# l-drv_h1.net
KiCad netlist of a schematic drawn in EAGLE
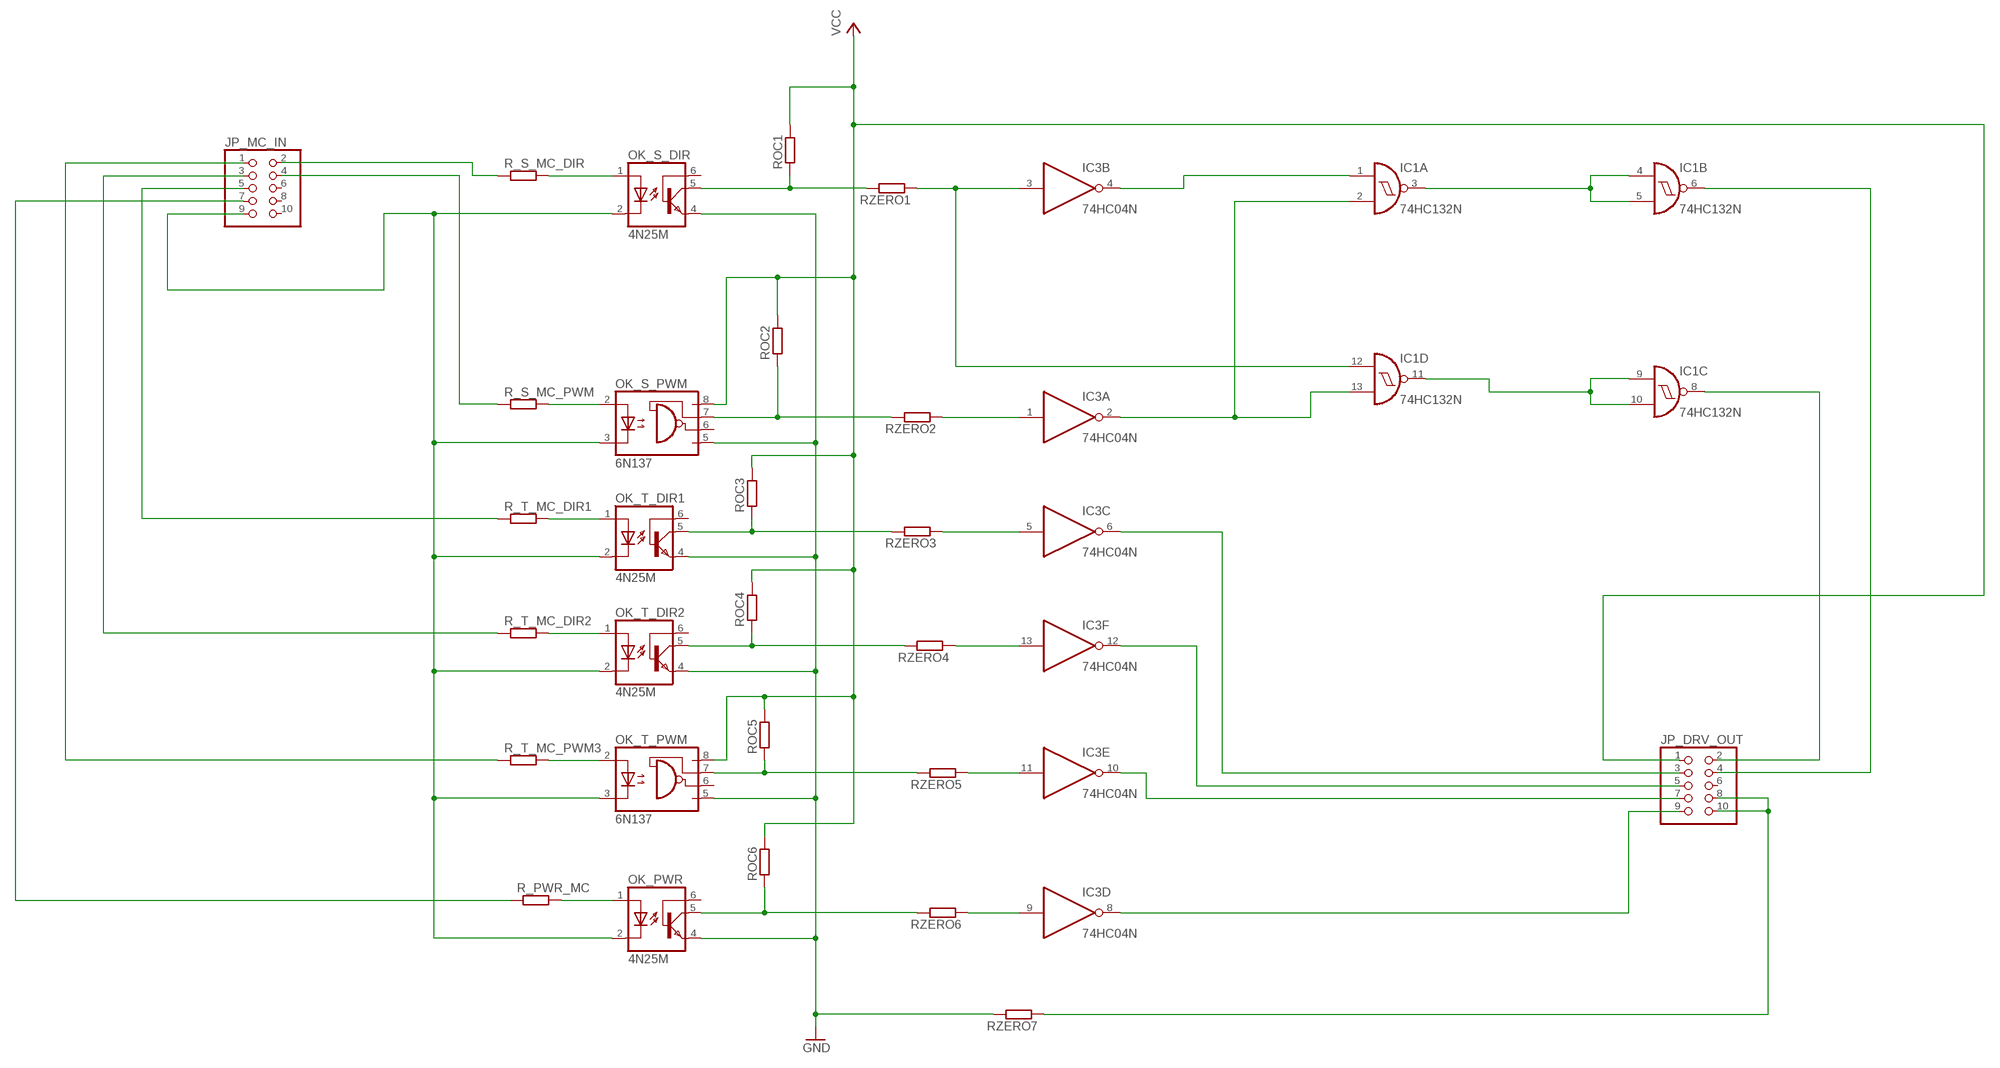
[diagram p0: schematic, sheet 1]

(export (version "E")
  (design (tool "Eeschema 10.0.6"))
  (components
    (comp (ref "IC1")
      (value "74HC132N")
      (footprint "eagle-import:DIL14")
      (libsource (lib "eagle-import") (part "74132NHC"))
    )
    (comp (ref "IC3")
      (value "74HC04N")
      (footprint "eagle-import:DIL14")
      (libsource (lib "eagle-import") (part "7404NHC"))
    )
    (comp (ref "JP_DRV_OUT")
      (value "PINHD-2X5/90")
      (footprint "eagle-import:2X05_90")
      (libsource (lib "eagle-import") (part "PINHD-2X5/90"))
    )
    (comp (ref "JP_MC_IN")
      (value "PINHD-2X5")
      (footprint "eagle-import:2X05")
      (libsource (lib "eagle-import") (part "PINHD-2X5"))
    )
    (comp (ref "OK_PWR")
      (value "4N25M")
      (footprint "eagle-import:DIL06")
      (fields (field (name "MPN") "4N25-M"))
      (libsource (lib "eagle-import") (part "4N?M25"))
    )
    (comp (ref "OK_S_DIR")
      (value "4N25M")
      (footprint "eagle-import:DIL06")
      (fields (field (name "MPN") "4N25-M"))
      (libsource (lib "eagle-import") (part "4N?M25"))
    )
    (comp (ref "OK_S_PWM")
      (value "6N137")
      (footprint "eagle-import:DIL08")
      (libsource (lib "eagle-import") (part "6N137"))
    )
    (comp (ref "OK_T_DIR1")
      (value "4N25M")
      (footprint "eagle-import:DIL06")
      (fields (field (name "MPN") "4N25-M"))
      (libsource (lib "eagle-import") (part "4N?M25"))
    )
    (comp (ref "OK_T_DIR2")
      (value "4N25M")
      (footprint "eagle-import:DIL06")
      (fields (field (name "MPN") "4N25-M"))
      (libsource (lib "eagle-import") (part "4N?M25"))
    )
    (comp (ref "OK_T_PWM")
      (value "6N137")
      (footprint "eagle-import:DIL08")
      (libsource (lib "eagle-import") (part "6N137"))
    )
    (comp (ref "ROC1")
      (value "R-EU_0204/5")
      (footprint "eagle-import:0204_5")
      (libsource (lib "eagle-import") (part "R-EU_0204/5"))
    )
    (comp (ref "ROC2")
      (value "R-EU_0204/5")
      (footprint "eagle-import:0204_5")
      (libsource (lib "eagle-import") (part "R-EU_0204/5"))
    )
    (comp (ref "ROC3")
      (value "R-EU_0204/5")
      (footprint "eagle-import:0204_5")
      (libsource (lib "eagle-import") (part "R-EU_0204/5"))
    )
    (comp (ref "ROC4")
      (value "R-EU_0204/5")
      (footprint "eagle-import:0204_5")
      (libsource (lib "eagle-import") (part "R-EU_0204/5"))
    )
    (comp (ref "ROC5")
      (value "R-EU_0204/5")
      (footprint "eagle-import:0204_5")
      (libsource (lib "eagle-import") (part "R-EU_0204/5"))
    )
    (comp (ref "ROC6")
      (value "R-EU_0204/5")
      (footprint "eagle-import:0204_5")
      (libsource (lib "eagle-import") (part "R-EU_0204/5"))
    )
    (comp (ref "RZERO1")
      (value "R-EU_0204/5")
      (footprint "eagle-import:0204_5")
      (libsource (lib "eagle-import") (part "R-EU_0204/5"))
    )
    (comp (ref "RZERO2")
      (value "R-EU_0204/5")
      (footprint "eagle-import:0204_5")
      (libsource (lib "eagle-import") (part "R-EU_0204/5"))
    )
    (comp (ref "RZERO3")
      (value "R-EU_0204/5")
      (footprint "eagle-import:0204_5")
      (libsource (lib "eagle-import") (part "R-EU_0204/5"))
    )
    (comp (ref "RZERO4")
      (value "R-EU_0204/5")
      (footprint "eagle-import:0204_5")
      (libsource (lib "eagle-import") (part "R-EU_0204/5"))
    )
    (comp (ref "RZERO5")
      (value "R-EU_0204/5")
      (footprint "eagle-import:0204_5")
      (libsource (lib "eagle-import") (part "R-EU_0204/5"))
    )
    (comp (ref "RZERO6")
      (value "R-EU_0204/5")
      (footprint "eagle-import:0204_5")
      (libsource (lib "eagle-import") (part "R-EU_0204/5"))
    )
    (comp (ref "RZERO7")
      (value "R-EU_0204/5")
      (footprint "eagle-import:0204_5")
      (libsource (lib "eagle-import") (part "R-EU_0204/5"))
    )
    (comp (ref "R_PWR_MC")
      (value "R-EU_0204/5")
      (footprint "eagle-import:0204_5")
      (libsource (lib "eagle-import") (part "R-EU_0204/5"))
    )
    (comp (ref "R_S_MC_DIR")
      (value "R-EU_0204/5")
      (footprint "eagle-import:0204_5")
      (libsource (lib "eagle-import") (part "R-EU_0204/5"))
    )
    (comp (ref "R_S_MC_PWM")
      (value "R-EU_0204/5")
      (footprint "eagle-import:0204_5")
      (libsource (lib "eagle-import") (part "R-EU_0204/5"))
    )
    (comp (ref "R_T_MC_DIR1")
      (value "R-EU_0204/5")
      (footprint "eagle-import:0204_5")
      (libsource (lib "eagle-import") (part "R-EU_0204/5"))
    )
    (comp (ref "R_T_MC_DIR2")
      (value "R-EU_0204/5")
      (footprint "eagle-import:0204_5")
      (libsource (lib "eagle-import") (part "R-EU_0204/5"))
    )
    (comp (ref "R_T_MC_PWM3")
      (value "R-EU_0204/5")
      (footprint "eagle-import:0204_5")
      (libsource (lib "eagle-import") (part "R-EU_0204/5"))
    )
  )
  (nets
    (net (code "1") (name "GND") (class "Default")
      (node (ref "OK_PWR") (pin "4") (pinfunction "EMI_4") (pintype "passive"))
      (node (ref "OK_S_DIR") (pin "4") (pinfunction "EMI_4") (pintype "passive"))
      (node (ref "OK_S_PWM") (pin "5") (pinfunction "GND_5") (pintype "passive"))
      (node (ref "OK_T_DIR1") (pin "4") (pinfunction "EMI_4") (pintype "passive"))
      (node (ref "OK_T_DIR2") (pin "4") (pinfunction "EMI_4") (pintype "passive"))
      (node (ref "OK_T_PWM") (pin "5") (pinfunction "GND_5") (pintype "passive"))
      (node (ref "RZERO7") (pin "2") (pinfunction "2_2") (pintype "passive"))
    )
    (net (code "2") (name "Net-(IC1A-I0)") (class "Default")
      (node (ref "IC1") (pin "1") (pinfunction "I0_1") (pintype "input"))
      (node (ref "IC3") (pin "4") (pinfunction "O_4") (pintype "output"))
    )
    (net (code "3") (name "Net-(IC1A-I1)") (class "Default")
      (node (ref "IC1") (pin "13") (pinfunction "I1_13") (pintype "input"))
      (node (ref "IC1") (pin "2") (pinfunction "I1_2") (pintype "input"))
      (node (ref "IC3") (pin "2") (pinfunction "O_2") (pintype "output"))
    )
    (net (code "4") (name "Net-(IC1A-O)") (class "Default")
      (node (ref "IC1") (pin "3") (pinfunction "O_3") (pintype "output"))
      (node (ref "IC1") (pin "4") (pinfunction "I0_4") (pintype "input"))
      (node (ref "IC1") (pin "5") (pinfunction "I1_5") (pintype "input"))
    )
    (net (code "5") (name "Net-(IC1B-O)") (class "Default")
      (node (ref "IC1") (pin "6") (pinfunction "O_6") (pintype "output"))
      (node (ref "JP_DRV_OUT") (pin "4") (pinfunction "4_4") (pintype "passive"))
    )
    (net (code "6") (name "Net-(IC1C-I0)") (class "Default")
      (node (ref "IC1") (pin "10") (pinfunction "I1_10") (pintype "input"))
      (node (ref "IC1") (pin "11") (pinfunction "O_11") (pintype "output"))
      (node (ref "IC1") (pin "9") (pinfunction "I0_9") (pintype "input"))
    )
    (net (code "7") (name "Net-(IC1C-O)") (class "Default")
      (node (ref "IC1") (pin "8") (pinfunction "O_8") (pintype "output"))
      (node (ref "JP_DRV_OUT") (pin "2") (pinfunction "2_2") (pintype "passive"))
    )
    (net (code "8") (name "Net-(IC1D-I0)") (class "Default")
      (node (ref "IC1") (pin "12") (pinfunction "I0_12") (pintype "input"))
      (node (ref "IC3") (pin "3") (pinfunction "I_3") (pintype "input"))
      (node (ref "RZERO1") (pin "1") (pinfunction "1_1") (pintype "passive"))
    )
    (net (code "9") (name "Net-(IC3A-I)") (class "Default")
      (node (ref "IC3") (pin "1") (pinfunction "I_1") (pintype "input"))
      (node (ref "RZERO2") (pin "1") (pinfunction "1_1") (pintype "passive"))
    )
    (net (code "10") (name "Net-(IC3C-I)") (class "Default")
      (node (ref "IC3") (pin "5") (pinfunction "I_5") (pintype "input"))
      (node (ref "RZERO3") (pin "1") (pinfunction "1_1") (pintype "passive"))
    )
    (net (code "11") (name "Net-(IC3C-O)") (class "Default")
      (node (ref "IC3") (pin "6") (pinfunction "O_6") (pintype "output"))
      (node (ref "JP_DRV_OUT") (pin "3") (pinfunction "3_3") (pintype "passive"))
    )
    (net (code "12") (name "Net-(IC3D-I)") (class "Default")
      (node (ref "IC3") (pin "9") (pinfunction "I_9") (pintype "input"))
      (node (ref "RZERO6") (pin "1") (pinfunction "1_1") (pintype "passive"))
    )
    (net (code "13") (name "Net-(IC3D-O)") (class "Default")
      (node (ref "IC3") (pin "8") (pinfunction "O_8") (pintype "output"))
      (node (ref "JP_DRV_OUT") (pin "9") (pinfunction "9_9") (pintype "passive"))
    )
    (net (code "14") (name "Net-(IC3E-I)") (class "Default")
      (node (ref "IC3") (pin "11") (pinfunction "I_11") (pintype "input"))
      (node (ref "RZERO5") (pin "1") (pinfunction "1_1") (pintype "passive"))
    )
    (net (code "15") (name "Net-(IC3E-O)") (class "Default")
      (node (ref "IC3") (pin "10") (pinfunction "O_10") (pintype "output"))
      (node (ref "JP_DRV_OUT") (pin "7") (pinfunction "7_7") (pintype "passive"))
    )
    (net (code "16") (name "Net-(IC3F-I)") (class "Default")
      (node (ref "IC3") (pin "13") (pinfunction "I_13") (pintype "input"))
      (node (ref "RZERO4") (pin "1") (pinfunction "1_1") (pintype "passive"))
    )
    (net (code "17") (name "Net-(IC3F-O)") (class "Default")
      (node (ref "IC3") (pin "12") (pinfunction "O_12") (pintype "output"))
      (node (ref "JP_DRV_OUT") (pin "5") (pinfunction "5_5") (pintype "passive"))
    )
    (net (code "18") (name "Net-(JP_DRV_OUT-Pad10)") (class "Default")
      (node (ref "JP_DRV_OUT") (pin "10") (pinfunction "10_10") (pintype "passive"))
      (node (ref "JP_DRV_OUT") (pin "8") (pinfunction "8_8") (pintype "passive"))
      (node (ref "RZERO7") (pin "1") (pinfunction "1_1") (pintype "passive"))
    )
    (net (code "19") (name "Net-(JP_MC_IN-Pad1)") (class "Default")
      (node (ref "JP_MC_IN") (pin "1") (pinfunction "1_1") (pintype "passive"))
      (node (ref "R_T_MC_PWM3") (pin "1") (pinfunction "1_1") (pintype "passive"))
    )
    (net (code "20") (name "Net-(JP_MC_IN-Pad2)") (class "Default")
      (node (ref "JP_MC_IN") (pin "2") (pinfunction "2_2") (pintype "passive"))
      (node (ref "R_S_MC_DIR") (pin "1") (pinfunction "1_1") (pintype "passive"))
    )
    (net (code "21") (name "Net-(JP_MC_IN-Pad3)") (class "Default")
      (node (ref "JP_MC_IN") (pin "3") (pinfunction "3_3") (pintype "passive"))
      (node (ref "R_T_MC_DIR2") (pin "1") (pinfunction "1_1") (pintype "passive"))
    )
    (net (code "22") (name "Net-(JP_MC_IN-Pad4)") (class "Default")
      (node (ref "JP_MC_IN") (pin "4") (pinfunction "4_4") (pintype "passive"))
      (node (ref "R_S_MC_PWM") (pin "1") (pinfunction "1_1") (pintype "passive"))
    )
    (net (code "23") (name "Net-(JP_MC_IN-Pad5)") (class "Default")
      (node (ref "JP_MC_IN") (pin "5") (pinfunction "5_5") (pintype "passive"))
      (node (ref "R_T_MC_DIR1") (pin "1") (pinfunction "1_1") (pintype "passive"))
    )
    (net (code "24") (name "Net-(JP_MC_IN-Pad7)") (class "Default")
      (node (ref "JP_MC_IN") (pin "7") (pinfunction "7_7") (pintype "passive"))
      (node (ref "R_PWR_MC") (pin "1") (pinfunction "1_1") (pintype "passive"))
    )
    (net (code "25") (name "Net-(OK_PWR-A)") (class "Default")
      (node (ref "OK_PWR") (pin "1") (pinfunction "A_1") (pintype "passive"))
      (node (ref "R_PWR_MC") (pin "2") (pinfunction "2_2") (pintype "passive"))
    )
    (net (code "26") (name "Net-(OK_PWR-C)") (class "Default")
      (node (ref "JP_MC_IN") (pin "9") (pinfunction "9_9") (pintype "passive"))
      (node (ref "OK_PWR") (pin "2") (pinfunction "C_2") (pintype "passive"))
      (node (ref "OK_S_DIR") (pin "2") (pinfunction "C_2") (pintype "passive"))
      (node (ref "OK_S_PWM") (pin "3") (pinfunction "C_3") (pintype "passive"))
      (node (ref "OK_T_DIR1") (pin "2") (pinfunction "C_2") (pintype "passive"))
      (node (ref "OK_T_DIR2") (pin "2") (pinfunction "C_2") (pintype "passive"))
      (node (ref "OK_T_PWM") (pin "3") (pinfunction "C_3") (pintype "passive"))
    )
    (net (code "27") (name "Net-(OK_PWR-COL)") (class "Default")
      (node (ref "OK_PWR") (pin "5") (pinfunction "COL_5") (pintype "passive"))
      (node (ref "ROC6") (pin "1") (pinfunction "1_1") (pintype "passive"))
      (node (ref "RZERO6") (pin "2") (pinfunction "2_2") (pintype "passive"))
    )
    (net (code "28") (name "Net-(OK_S_DIR-A)") (class "Default")
      (node (ref "OK_S_DIR") (pin "1") (pinfunction "A_1") (pintype "passive"))
      (node (ref "R_S_MC_DIR") (pin "2") (pinfunction "2_2") (pintype "passive"))
    )
    (net (code "29") (name "Net-(OK_S_DIR-COL)") (class "Default")
      (node (ref "OK_S_DIR") (pin "5") (pinfunction "COL_5") (pintype "passive"))
      (node (ref "ROC1") (pin "1") (pinfunction "1_1") (pintype "passive"))
      (node (ref "RZERO1") (pin "2") (pinfunction "2_2") (pintype "passive"))
    )
    (net (code "30") (name "Net-(OK_S_PWM-A)") (class "Default")
      (node (ref "OK_S_PWM") (pin "2") (pinfunction "A_2") (pintype "passive"))
      (node (ref "R_S_MC_PWM") (pin "2") (pinfunction "2_2") (pintype "passive"))
    )
    (net (code "31") (name "Net-(OK_S_PWM-VE)") (class "Default")
      (node (ref "OK_S_PWM") (pin "7") (pinfunction "VE_7") (pintype "passive"))
      (node (ref "ROC2") (pin "1") (pinfunction "1_1") (pintype "passive"))
      (node (ref "RZERO2") (pin "2") (pinfunction "2_2") (pintype "passive"))
    )
    (net (code "32") (name "Net-(OK_T_DIR1-A)") (class "Default")
      (node (ref "OK_T_DIR1") (pin "1") (pinfunction "A_1") (pintype "passive"))
      (node (ref "R_T_MC_DIR1") (pin "2") (pinfunction "2_2") (pintype "passive"))
    )
    (net (code "33") (name "Net-(OK_T_DIR1-COL)") (class "Default")
      (node (ref "OK_T_DIR1") (pin "5") (pinfunction "COL_5") (pintype "passive"))
      (node (ref "ROC3") (pin "1") (pinfunction "1_1") (pintype "passive"))
      (node (ref "RZERO3") (pin "2") (pinfunction "2_2") (pintype "passive"))
    )
    (net (code "34") (name "Net-(OK_T_DIR2-A)") (class "Default")
      (node (ref "OK_T_DIR2") (pin "1") (pinfunction "A_1") (pintype "passive"))
      (node (ref "R_T_MC_DIR2") (pin "2") (pinfunction "2_2") (pintype "passive"))
    )
    (net (code "35") (name "Net-(OK_T_DIR2-COL)") (class "Default")
      (node (ref "OK_T_DIR2") (pin "5") (pinfunction "COL_5") (pintype "passive"))
      (node (ref "ROC4") (pin "1") (pinfunction "1_1") (pintype "passive"))
      (node (ref "RZERO4") (pin "2") (pinfunction "2_2") (pintype "passive"))
    )
    (net (code "36") (name "Net-(OK_T_PWM-A)") (class "Default")
      (node (ref "OK_T_PWM") (pin "2") (pinfunction "A_2") (pintype "passive"))
      (node (ref "R_T_MC_PWM3") (pin "2") (pinfunction "2_2") (pintype "passive"))
    )
    (net (code "37") (name "Net-(OK_T_PWM-VE)") (class "Default")
      (node (ref "OK_T_PWM") (pin "7") (pinfunction "VE_7") (pintype "passive"))
      (node (ref "ROC5") (pin "1") (pinfunction "1_1") (pintype "passive"))
      (node (ref "RZERO5") (pin "2") (pinfunction "2_2") (pintype "passive"))
    )
    (net (code "38") (name "VCC") (class "Default")
      (node (ref "JP_DRV_OUT") (pin "1") (pinfunction "1_1") (pintype "passive"))
      (node (ref "OK_S_PWM") (pin "8") (pinfunction "VCC_8") (pintype "passive"))
      (node (ref "OK_T_PWM") (pin "8") (pinfunction "VCC_8") (pintype "passive"))
      (node (ref "ROC1") (pin "2") (pinfunction "2_2") (pintype "passive"))
      (node (ref "ROC2") (pin "2") (pinfunction "2_2") (pintype "passive"))
      (node (ref "ROC3") (pin "2") (pinfunction "2_2") (pintype "passive"))
      (node (ref "ROC4") (pin "2") (pinfunction "2_2") (pintype "passive"))
      (node (ref "ROC5") (pin "2") (pinfunction "2_2") (pintype "passive"))
      (node (ref "ROC6") (pin "2") (pinfunction "2_2") (pintype "passive"))
    )
    (net (code "39") (name "unconnected-(JP_DRV_OUT-Pad6)") (class "Default")
      (node (ref "JP_DRV_OUT") (pin "6") (pinfunction "6_6") (pintype "passive"))
    )
    (net (code "40") (name "unconnected-(JP_MC_IN-Pad6)") (class "Default")
      (node (ref "JP_MC_IN") (pin "6") (pinfunction "6_6") (pintype "passive"))
    )
    (net (code "41") (name "unconnected-(JP_MC_IN-Pad8)") (class "Default")
      (node (ref "JP_MC_IN") (pin "8") (pinfunction "8_8") (pintype "passive"))
    )
    (net (code "42") (name "unconnected-(JP_MC_IN-Pad10)") (class "Default")
      (node (ref "JP_MC_IN") (pin "10") (pinfunction "10_10") (pintype "passive"))
    )
    (net (code "43") (name "unconnected-(OK_PWR-BAS-Pad6)") (class "Default")
      (node (ref "OK_PWR") (pin "6") (pinfunction "BAS_6") (pintype "passive"))
    )
    (net (code "44") (name "unconnected-(OK_S_DIR-BAS-Pad6)") (class "Default")
      (node (ref "OK_S_DIR") (pin "6") (pinfunction "BAS_6") (pintype "passive"))
    )
    (net (code "45") (name "unconnected-(OK_S_PWM-VO-Pad6)") (class "Default")
      (node (ref "OK_S_PWM") (pin "6") (pinfunction "VO_6") (pintype "passive"))
    )
    (net (code "46") (name "unconnected-(OK_T_DIR1-BAS-Pad6)") (class "Default")
      (node (ref "OK_T_DIR1") (pin "6") (pinfunction "BAS_6") (pintype "passive"))
    )
    (net (code "47") (name "unconnected-(OK_T_DIR2-BAS-Pad6)") (class "Default")
      (node (ref "OK_T_DIR2") (pin "6") (pinfunction "BAS_6") (pintype "passive"))
    )
    (net (code "48") (name "unconnected-(OK_T_PWM-VO-Pad6)") (class "Default")
      (node (ref "OK_T_PWM") (pin "6") (pinfunction "VO_6") (pintype "passive"))
    )
  )
)
